# Moto_Power_Supply_4x12v_4x5v.net
KiCad netlist of a schematic drawn in Altium Designer
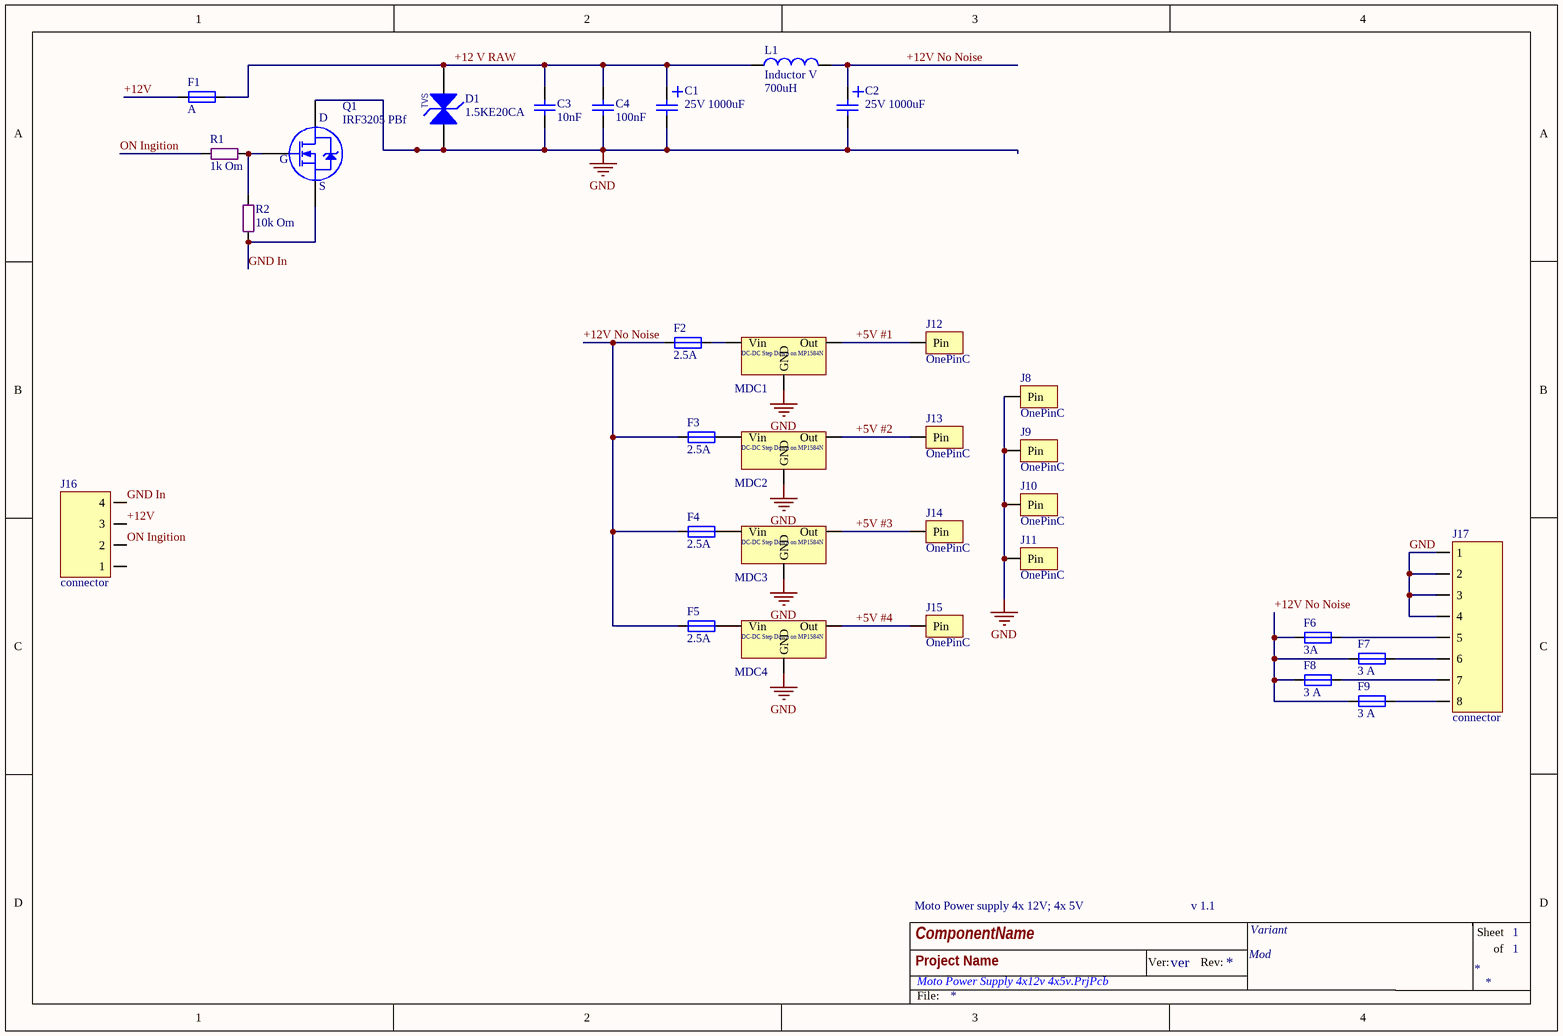
[diagram p0: Moto Power Supply 4x12v 4x5v.SchDoc]

(export (version "E")
  (design (tool "Eeschema 10.0.6"))
  (components
    (comp (ref "C1")
      (value "25V 1000uF")
      (footprint "Capacitor:Cap E p5.08mm D10.2mm (3p)")
      (description "Capacitor")
      (libsource (lib "Capacitor") (part "Cap E 1000mF x 25V"))
    )
    (comp (ref "C2")
      (value "25V 1000uF")
      (footprint "Capacitor:Cap E p5.08mm D10.2mm (3p)")
      (description "Capacitor")
      (libsource (lib "Capacitor") (part "Cap E 1000mF x 25V"))
    )
    (comp (ref "C3")
      (value "10nF")
      (footprint "Capacitor:SMD 1206 (3216)")
      (description "Capacitor")
      (libsource (lib "Capacitor") (part "Cap Ceramic SMD (All)"))
    )
    (comp (ref "C4")
      (value "100nF")
      (footprint "Capacitor:SMD 1206 (3216)")
      (description "Capacitor")
      (libsource (lib "Capacitor") (part "Cap Ceramic SMD (All)"))
    )
    (comp (ref "D1")
      (value "1.5KE20CA")
      (footprint "Diodes:TVS diode DO-201 V")
      (description "1500W Transil (TVS Diode)")
      (libsource (lib "Diodes") (part "TVS 1.5KE20CA"))
    )
    (comp (ref "F1")
      (value "A")
      (footprint "PassiveComponents:Fuse RGE1100")
      (description "Round fuse")
      (libsource (lib "PassiveComponents") (part "Fuse"))
    )
    (comp (ref "F2")
      (value "2.5A")
      (footprint "PassiveComponents:Fuse SM250")
      (description "Round fuse")
      (libsource (lib "PassiveComponents") (part "Fuse"))
    )
    (comp (ref "F3")
      (value "2.5A")
      (footprint "PassiveComponents:Fuse SM250")
      (description "Round fuse")
      (libsource (lib "PassiveComponents") (part "Fuse"))
    )
    (comp (ref "F4")
      (value "2.5A")
      (footprint "PassiveComponents:Fuse SM250")
      (description "Round fuse")
      (libsource (lib "PassiveComponents") (part "Fuse"))
    )
    (comp (ref "F5")
      (value "2.5A")
      (footprint "PassiveComponents:Fuse SM250")
      (description "Round fuse")
      (libsource (lib "PassiveComponents") (part "Fuse"))
    )
    (comp (ref "F6")
      (value "3A")
      (footprint "PassiveComponents:Fuse MF-R300 (3A)")
      (description "Round fuse")
      (libsource (lib "PassiveComponents") (part "Fuse"))
    )
    (comp (ref "F7")
      (value "3 A")
      (footprint "PassiveComponents:Fuse MF-R300 (3A)")
      (description "Round fuse")
      (libsource (lib "PassiveComponents") (part "Fuse"))
    )
    (comp (ref "F8")
      (value "3 A")
      (footprint "PassiveComponents:Fuse MF-R300 (3A)")
      (description "Round fuse")
      (libsource (lib "PassiveComponents") (part "Fuse"))
    )
    (comp (ref "F9")
      (value "3 A")
      (footprint "PassiveComponents:Fuse MF-R300 (3A)")
      (description "Round fuse")
      (libsource (lib "PassiveComponents") (part "Fuse"))
    )
    (comp (ref "J8")
      (value "OnePinC")
      (footprint "Connector:OnePin 1.2x3")
      (description "Only pad")
      (libsource (lib "Connector") (part "OnePin Connector"))
    )
    (comp (ref "J9")
      (value "OnePinC")
      (footprint "Connector:OnePin 1.2x3")
      (description "Only pad")
      (libsource (lib "Connector") (part "OnePin Connector"))
    )
    (comp (ref "J10")
      (value "OnePinC")
      (footprint "Connector:OnePin 1.2x3")
      (description "Only pad")
      (libsource (lib "Connector") (part "OnePin Connector"))
    )
    (comp (ref "J11")
      (value "OnePinC")
      (footprint "Connector:OnePin 1.2x3")
      (description "Only pad")
      (libsource (lib "Connector") (part "OnePin Connector"))
    )
    (comp (ref "J12")
      (value "OnePinC")
      (footprint "Connector:OnePin 1.2x3")
      (description "Only pad")
      (libsource (lib "Connector") (part "OnePin Connector"))
    )
    (comp (ref "J13")
      (value "OnePinC")
      (footprint "Connector:OnePin 1.2x3")
      (description "Only pad")
      (libsource (lib "Connector") (part "OnePin Connector"))
    )
    (comp (ref "J14")
      (value "OnePinC")
      (footprint "Connector:OnePin 1.2x3")
      (description "Only pad")
      (libsource (lib "Connector") (part "OnePin Connector"))
    )
    (comp (ref "J15")
      (value "OnePinC")
      (footprint "Connector:OnePin 1.2x3")
      (description "Only pad")
      (libsource (lib "Connector") (part "OnePin Connector"))
    )
    (comp (ref "J16")
      (value "connector")
      (footprint "Connector:Molex Mini-Fit Jr - 4Pin V")
      (description "Right, Dbl line, Female")
      (libsource (lib "Connector") (part "Molex Mini-Fit Jr - 4 pin"))
    )
    (comp (ref "J17")
      (value "connector")
      (footprint "Connector:Molex Mini-Fit Jr - 8Pin V")
      (description "Right, Dbl line, Female")
      (libsource (lib "Connector") (part "Molex Mini-Fit Jr - 8 pin"))
    )
    (comp (ref "L1")
      (value "Inductor V")
      (footprint "Transformers:Toroid V D14-W6")
      (description "Inductor Vertical")
      (fields (field (name "ALTIUM_VALUE") "700uH") (field (name "PUBLISHER") "Altium Limited"))
      (libsource (lib "Transformers") (part "Inductor V"))
    )
    (comp (ref "MDC1")
      (value "DC-DC")
      (footprint "Modules:DC-DC_MP1584N (SMALL R)")
      (description "DC-DC StepDown")
      (libsource (lib "Modules") (part "DC-DC MP1584N"))
    )
    (comp (ref "MDC2")
      (value "DC-DC")
      (footprint "Modules:DC-DC_MP1584N (SMALL R)")
      (description "DC-DC StepDown")
      (libsource (lib "Modules") (part "DC-DC MP1584N"))
    )
    (comp (ref "MDC3")
      (value "DC-DC")
      (footprint "Modules:DC-DC_MP1584N (SMALL R)")
      (description "DC-DC StepDown")
      (libsource (lib "Modules") (part "DC-DC MP1584N"))
    )
    (comp (ref "MDC4")
      (value "DC-DC")
      (footprint "Modules:DC-DC_MP1584N (SMALL R)")
      (description "DC-DC StepDown")
      (libsource (lib "Modules") (part "DC-DC MP1584N"))
    )
    (comp (ref "Q1")
      (value "IRF3205 PBf")
      (footprint "GeneralCases:TO220-2")
      (description "N-Channel 55V - 0.008Ω - 110A")
      (libsource (lib "Transistor") (part "IRF3205"))
    )
    (comp (ref "R1")
      (value "1k Om")
      (footprint "PassiveComponents:SMD 0805 (2012)")
      (libsource (lib "PassiveComponents") (part "Res All Types"))
    )
    (comp (ref "R2")
      (value "10k Om")
      (footprint "PassiveComponents:SMD 0805 (2012)")
      (libsource (lib "PassiveComponents") (part "Res All Types"))
    )
  )
  (nets
    (net (code "1") (name "/+5V #1") (class "Default")
      (node (ref "J12") (pin "1") (pinfunction "Pin_1") (pintype "passive"))
      (node (ref "MDC1") (pin "OUT") (pinfunction "Out_OUT") (pintype "passive"))
    )
    (net (code "2") (name "/+5V #2") (class "Default")
      (node (ref "J13") (pin "1") (pinfunction "Pin_1") (pintype "passive"))
      (node (ref "MDC2") (pin "OUT") (pinfunction "Out_OUT") (pintype "passive"))
    )
    (net (code "3") (name "/+5V #3") (class "Default")
      (node (ref "J14") (pin "1") (pinfunction "Pin_1") (pintype "passive"))
      (node (ref "MDC3") (pin "OUT") (pinfunction "Out_OUT") (pintype "passive"))
    )
    (net (code "4") (name "/+5V #4") (class "Default")
      (node (ref "J15") (pin "1") (pinfunction "Pin_1") (pintype "passive"))
      (node (ref "MDC4") (pin "OUT") (pinfunction "Out_OUT") (pintype "passive"))
    )
    (net (code "5") (name "/+12 V RAW") (class "Default")
      (node (ref "C1") (pin "1") (pinfunction "1_1") (pintype "passive"))
      (node (ref "C3") (pin "1") (pinfunction "1_1") (pintype "passive"))
      (node (ref "C4") (pin "1") (pinfunction "1_1") (pintype "passive"))
      (node (ref "D1") (pin "2") (pinfunction "2_2") (pintype "passive"))
      (node (ref "F1") (pin "2") (pinfunction "2_2") (pintype "passive"))
      (node (ref "L1") (pin "1") (pinfunction "1_1") (pintype "passive"))
    )
    (net (code "6") (name "/+12V") (class "Default")
      (node (ref "F1") (pin "1") (pinfunction "1_1") (pintype "passive"))
      (node (ref "J16") (pin "3") (pinfunction "3_3") (pintype "passive"))
    )
    (net (code "7") (name "/+12V No Noise") (class "Default")
      (node (ref "C2") (pin "1") (pinfunction "1_1") (pintype "passive"))
      (node (ref "F2") (pin "1") (pinfunction "1_1") (pintype "passive"))
      (node (ref "F3") (pin "1") (pinfunction "1_1") (pintype "passive"))
      (node (ref "F4") (pin "1") (pinfunction "1_1") (pintype "passive"))
      (node (ref "F5") (pin "1") (pinfunction "1_1") (pintype "passive"))
      (node (ref "F6") (pin "2") (pinfunction "2_2") (pintype "passive"))
      (node (ref "F7") (pin "2") (pinfunction "2_2") (pintype "passive"))
      (node (ref "F8") (pin "2") (pinfunction "2_2") (pintype "passive"))
      (node (ref "F9") (pin "2") (pinfunction "2_2") (pintype "passive"))
      (node (ref "L1") (pin "2") (pinfunction "2_2") (pintype "passive"))
    )
    (net (code "8") (name "/GND In") (class "Default")
      (node (ref "J16") (pin "4") (pinfunction "4_4") (pintype "passive"))
      (node (ref "Q1") (pin "3") (pinfunction "S_3") (pintype "passive"))
      (node (ref "R2") (pin "1") (pinfunction "1_1") (pintype "passive"))
    )
    (net (code "9") (name "/ON Ingition") (class "Default")
      (node (ref "J16") (pin "2") (pinfunction "2_2") (pintype "passive"))
      (node (ref "R1") (pin "1") (pinfunction "1_1") (pintype "passive"))
    )
    (net (code "10") (name "GND") (class "Default")
      (node (ref "C1") (pin "2") (pinfunction "2_2") (pintype "passive"))
      (node (ref "C2") (pin "2") (pinfunction "2_2") (pintype "passive"))
      (node (ref "C3") (pin "2") (pinfunction "2_2") (pintype "passive"))
      (node (ref "C4") (pin "2") (pinfunction "2_2") (pintype "passive"))
      (node (ref "D1") (pin "1") (pinfunction "1_1") (pintype "passive"))
      (node (ref "J10") (pin "1") (pinfunction "Pin_1") (pintype "passive"))
      (node (ref "J11") (pin "1") (pinfunction "Pin_1") (pintype "passive"))
      (node (ref "J17") (pin "1") (pinfunction "1_1") (pintype "passive"))
      (node (ref "J17") (pin "2") (pinfunction "2_2") (pintype "passive"))
      (node (ref "J17") (pin "3") (pinfunction "3_3") (pintype "passive"))
      (node (ref "J17") (pin "4") (pinfunction "4_4") (pintype "passive"))
      (node (ref "J8") (pin "1") (pinfunction "Pin_1") (pintype "passive"))
      (node (ref "J9") (pin "1") (pinfunction "Pin_1") (pintype "passive"))
      (node (ref "MDC1") (pin "GND") (pinfunction "GND_GND") (pintype "passive"))
      (node (ref "MDC2") (pin "GND") (pinfunction "GND_GND") (pintype "passive"))
      (node (ref "MDC3") (pin "GND") (pinfunction "GND_GND") (pintype "passive"))
      (node (ref "MDC4") (pin "GND") (pinfunction "GND_GND") (pintype "passive"))
      (node (ref "Q1") (pin "2") (pinfunction "D_2") (pintype "passive"))
    )
    (net (code "11") (name "Net-(F6-Pad1)") (class "Default")
      (node (ref "F6") (pin "1") (pinfunction "1_1") (pintype "passive"))
      (node (ref "J17") (pin "5") (pinfunction "5_5") (pintype "passive"))
    )
    (net (code "12") (name "Net-(F7-Pad1)") (class "Default")
      (node (ref "F7") (pin "1") (pinfunction "1_1") (pintype "passive"))
      (node (ref "J17") (pin "6") (pinfunction "6_6") (pintype "passive"))
    )
    (net (code "13") (name "Net-(F8-Pad1)") (class "Default")
      (node (ref "F8") (pin "1") (pinfunction "1_1") (pintype "passive"))
      (node (ref "J17") (pin "7") (pinfunction "7_7") (pintype "passive"))
    )
    (net (code "14") (name "Net-(F9-Pad1)") (class "Default")
      (node (ref "F9") (pin "1") (pinfunction "1_1") (pintype "passive"))
      (node (ref "J17") (pin "8") (pinfunction "8_8") (pintype "passive"))
    )
    (net (code "15") (name "Net-(MDC1-Vin)") (class "Default")
      (node (ref "F2") (pin "2") (pinfunction "2_2") (pintype "passive"))
      (node (ref "MDC1") (pin "IN") (pinfunction "Vin_IN") (pintype "passive"))
    )
    (net (code "16") (name "Net-(MDC2-Vin)") (class "Default")
      (node (ref "F3") (pin "2") (pinfunction "2_2") (pintype "passive"))
      (node (ref "MDC2") (pin "IN") (pinfunction "Vin_IN") (pintype "passive"))
    )
    (net (code "17") (name "Net-(MDC3-Vin)") (class "Default")
      (node (ref "F4") (pin "2") (pinfunction "2_2") (pintype "passive"))
      (node (ref "MDC3") (pin "IN") (pinfunction "Vin_IN") (pintype "passive"))
    )
    (net (code "18") (name "Net-(MDC4-Vin)") (class "Default")
      (node (ref "F5") (pin "2") (pinfunction "2_2") (pintype "passive"))
      (node (ref "MDC4") (pin "IN") (pinfunction "Vin_IN") (pintype "passive"))
    )
    (net (code "19") (name "Net-(Q1-G)") (class "Default")
      (node (ref "Q1") (pin "1") (pinfunction "G_1") (pintype "passive"))
      (node (ref "R1") (pin "2") (pinfunction "2_2") (pintype "passive"))
      (node (ref "R2") (pin "2") (pinfunction "2_2") (pintype "passive"))
    )
    (net (code "20") (name "unconnected-(J16-Pad1)") (class "Default")
      (node (ref "J16") (pin "1") (pinfunction "1_1") (pintype "passive"))
    )
  )
)
